# Power_Circuitry.net
KiCad netlist of a schematic drawn in Altium Designer
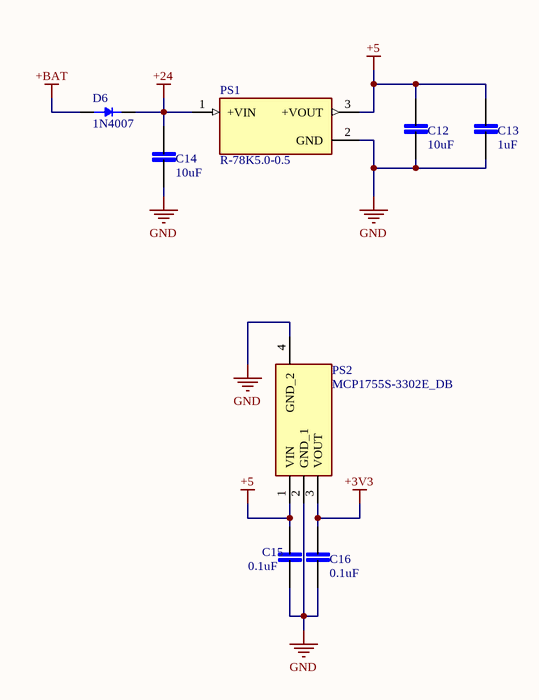
[diagram p0: Power Circuitry.SchDoc]

(export (version "E")
  (design (tool "Eeschema 10.0.6"))
  (components
    (comp (ref "C12")
      (value "10uF")
      (footprint "0805")
      (fields (field (name "MP") "LD051A121KAB2A") (field (name "MF") "AVX"))
      (libsource (lib "Capacitors SMD") (part "0805_Capacitor"))
    )
    (comp (ref "C13")
      (value "1uF")
      (footprint "0805")
      (fields (field (name "MP") "LD051A121KAB2A") (field (name "MF") "AVX"))
      (libsource (lib "Capacitors SMD") (part "0805_Capacitor"))
    )
    (comp (ref "C14")
      (value "10uF")
      (footprint "0805")
      (fields (field (name "MP") "LD051A121KAB2A") (field (name "MF") "AVX"))
      (libsource (lib "Capacitors SMD") (part "0805_Capacitor"))
    )
    (comp (ref "C15")
      (value "0.1uF")
      (footprint "0805")
      (fields (field (name "MP") "LD051A121KAB2A") (field (name "MF") "AVX"))
      (libsource (lib "Capacitors SMD") (part "0805_Capacitor"))
    )
    (comp (ref "C16")
      (value "0.1uF")
      (footprint "0805")
      (fields (field (name "MP") "LD051A121KAB2A") (field (name "MF") "AVX"))
      (libsource (lib "") (part "0805_Capacitor_1"))
    )
    (comp (ref "D6")
      (value "1N4007")
      (footprint "SOD123")
      (fields (field (name "MF") "Diodes Inc.") (field (name "MP") "1N4148W-7-F"))
      (libsource (lib "Diodes SMD") (part "SOD123 - Rectifier Diode"))
    )
    (comp (ref "PS1")
      (value "R-78K5.0-0.5")
      (footprint "CONV_R-78K5.0-0.5")
      (description "0.5A DC/DC-Converter 'INNOLINE' SIP3 reg")
      (fields (field (name "MF") "Recom Power"))
      (libsource (lib "Voltage Regulators Through Hole") (part "R-78K5.0-0.5"))
    )
    (comp (ref "PS2")
      (value "MCP1755S-3302E_DB")
      (footprint "Voltage Regulators SMD:MCP1755S-3302E_DB")
      (description "Power Supply")
      (fields
        (field (name "MANUFACTURER_PART_NUMBER") "MCP1755S-3302E/DB")
        (field (name "MOUSER PART NUMBER") "579-MCP1755S-3302EDB")
      )
      (libsource (lib "Voltage Regulators SMD") (part "MCP1755S-3302E_DB"))
    )
  )
  (nets
    (net (code "1") (name "+3V3") (class "Default")
      (node (ref "C16") (pin "2") (pinfunction "2_2") (pintype "passive"))
      (node (ref "PS2") (pin "3") (pinfunction "VOUT_3") (pintype "passive"))
    )
    (net (code "2") (name "+5") (class "Default")
      (node (ref "C12") (pin "2") (pinfunction "2_2") (pintype "passive"))
      (node (ref "C13") (pin "2") (pinfunction "2_2") (pintype "passive"))
      (node (ref "C15") (pin "2") (pinfunction "2_2") (pintype "passive"))
      (node (ref "PS1") (pin "3") (pinfunction "+VOUT_3") (pintype "output"))
      (node (ref "PS2") (pin "1") (pinfunction "VIN_1") (pintype "passive"))
    )
    (net (code "3") (name "+24") (class "Default")
      (node (ref "C14") (pin "2") (pinfunction "2_2") (pintype "passive"))
      (node (ref "D6") (pin "2") (pinfunction "A_2") (pintype "passive"))
      (node (ref "PS1") (pin "1") (pinfunction "+VIN_1") (pintype "input"))
    )
    (net (code "4") (name "+BAT") (class "Default")
      (node (ref "D6") (pin "1") (pinfunction "K_1") (pintype "passive"))
    )
    (net (code "5") (name "GND") (class "Default")
      (node (ref "C12") (pin "1") (pinfunction "1_1") (pintype "passive"))
      (node (ref "C13") (pin "1") (pinfunction "1_1") (pintype "passive"))
      (node (ref "C14") (pin "1") (pinfunction "1_1") (pintype "passive"))
      (node (ref "C15") (pin "1") (pinfunction "1_1") (pintype "passive"))
      (node (ref "C16") (pin "1") (pinfunction "1_1") (pintype "passive"))
      (node (ref "PS1") (pin "2") (pinfunction "GND_2") (pintype "power_in"))
      (node (ref "PS2") (pin "2") (pinfunction "GND_1_2") (pintype "passive"))
      (node (ref "PS2") (pin "4") (pinfunction "GND_2_4") (pintype "passive"))
    )
  )
)
